# ESC_Board_1.net
KiCad netlist of a schematic drawn in EAGLE
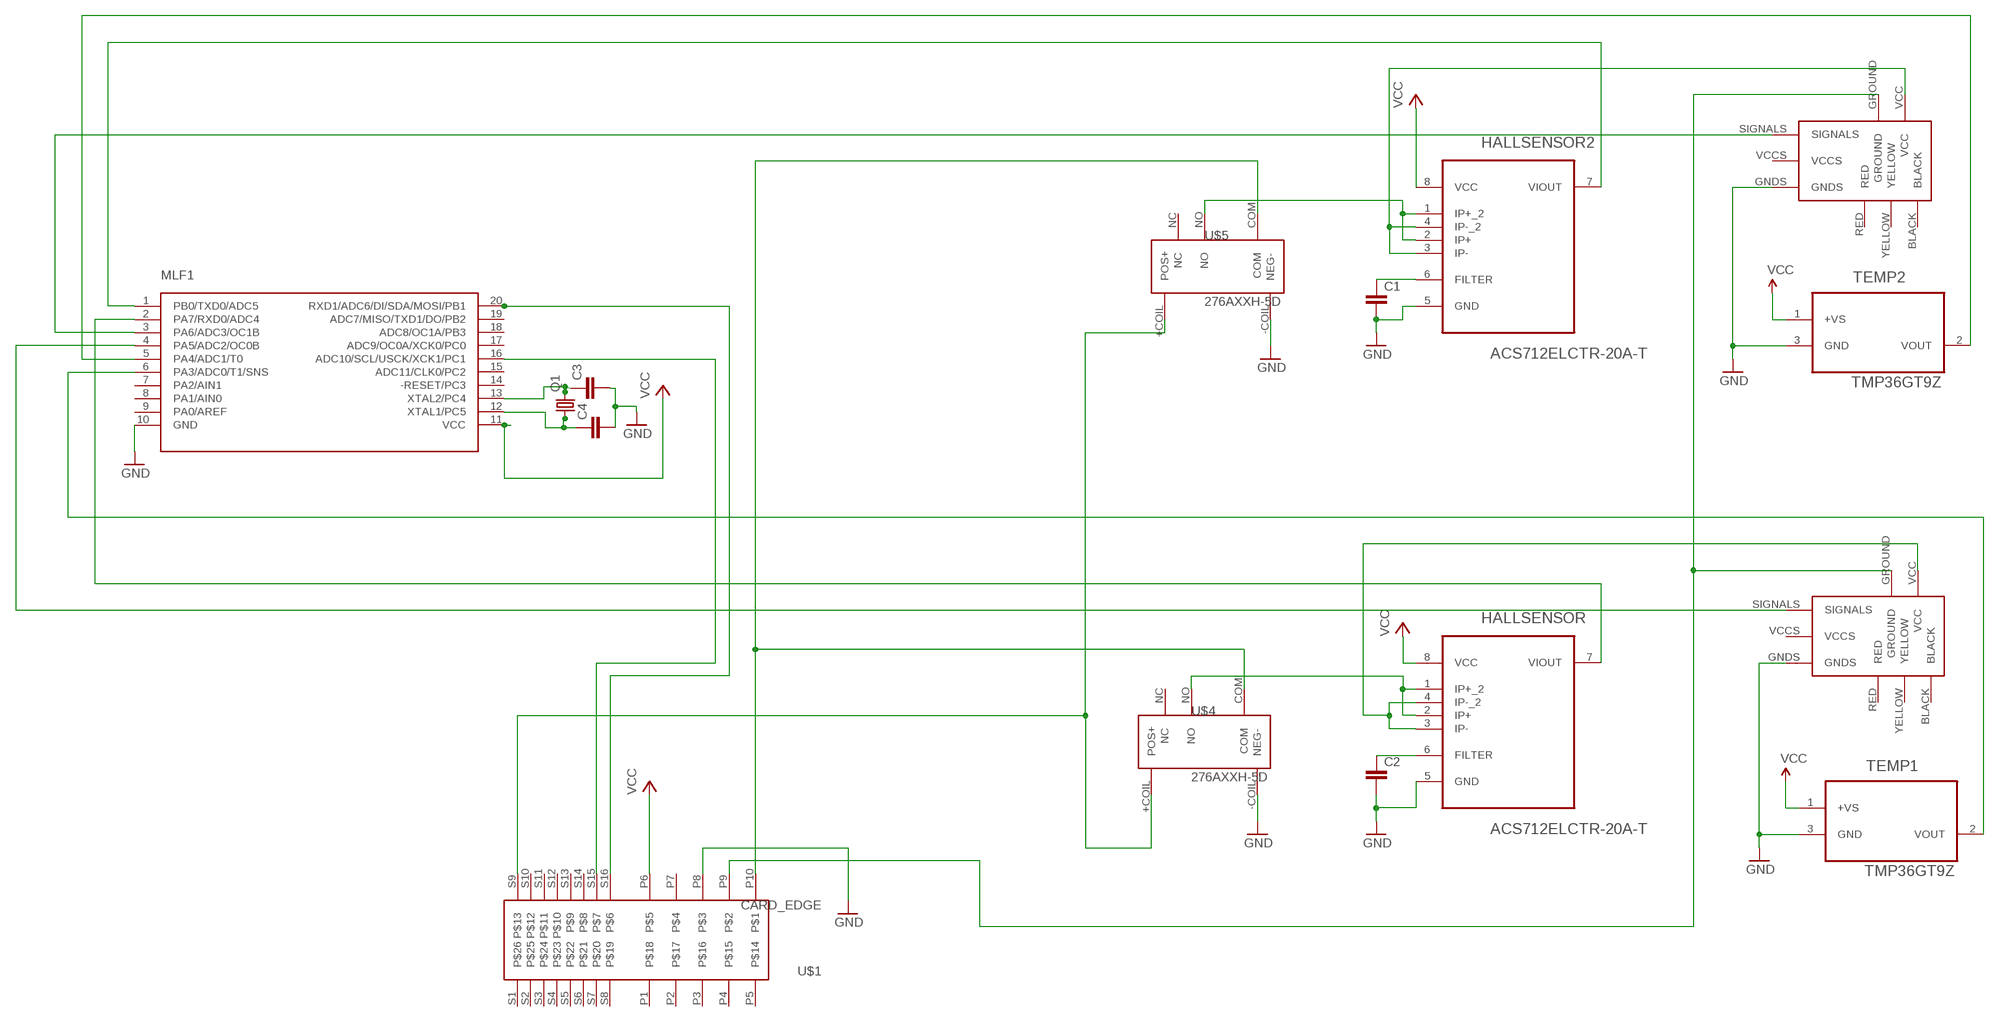
[diagram p0: schematic, sheet 1]

(export (version "E")
  (design (tool "Eeschema 10.0.6"))
  (components
    (comp (ref "C1")
      (value "CAPEZ")
      (footprint "eagle-import:CAP-PTH-SMALLEZ")
      (libsource (lib "eagle-import") (part "CAPEZ"))
    )
    (comp (ref "C2")
      (value "CAPEZ")
      (footprint "eagle-import:CAP-PTH-SMALLEZ")
      (libsource (lib "eagle-import") (part "CAPEZ"))
    )
    (comp (ref "C3")
      (value "CAPEZ")
      (footprint "eagle-import:CAP-PTH-SMALLEZ")
      (libsource (lib "eagle-import") (part "CAPEZ"))
    )
    (comp (ref "C4")
      (value "CAPEZ")
      (footprint "eagle-import:CAP-PTH-SMALLEZ")
      (libsource (lib "eagle-import") (part "CAPEZ"))
    )
    (comp (ref "HALLSENSOR")
      (value "ACS712ELCTR-20A-T")
      (footprint "eagle-import:SOIC127P600X175-8N")
      (libsource (lib "eagle-import") (part "ACS712ELCTR-20A-T"))
    )
    (comp (ref "HALLSENSOR2")
      (value "ACS712ELCTR-20A-T")
      (footprint "eagle-import:SOIC127P600X175-8N")
      (libsource (lib "eagle-import") (part "ACS712ELCTR-20A-T"))
    )
    (comp (ref "MLF1")
      (value "ATTINY1634SOIC20")
      (footprint "eagle-import:SOIC20")
      (libsource (lib "eagle-import") (part "ATTINY1634SOIC20"))
    )
    (comp (ref "Q1")
      (value "CRYTALTC26V")
      (footprint "eagle-import:TC26V")
      (libsource (lib "eagle-import") (part "CRYTALTC26V"))
    )
    (comp (ref "TEMP1")
      (value "TMP36GT9Z")
      (footprint "eagle-import:TO127P254X533-3P")
      (libsource (lib "eagle-import") (part "TMP36GT9Z"))
    )
    (comp (ref "TEMP2")
      (value "TMP36GT9Z")
      (footprint "eagle-import:TO127P254X533-3P")
      (libsource (lib "eagle-import") (part "TMP36GT9Z"))
    )
    (comp (ref "U$1")
      (value "CARD_EDGE")
      (footprint "eagle-import:EDGE_CONNECTOR")
      (libsource (lib "eagle-import") (part "CARD_EDGE"))
    )
    (comp (ref "U$2")
      (value "ESC30A")
      (footprint "eagle-import:30AESC")
      (libsource (lib "eagle-import") (part "ESC30A"))
    )
    (comp (ref "U$3")
      (value "ESC30A")
      (footprint "eagle-import:30AESC")
      (libsource (lib "eagle-import") (part "ESC30A"))
    )
    (comp (ref "U$4")
      (value "276AXXH-5D")
      (footprint "eagle-import:276AXXH-5D")
      (libsource (lib "eagle-import") (part "276AXXH-5D"))
    )
    (comp (ref "U$5")
      (value "276AXXH-5D")
      (footprint "eagle-import:276AXXH-5D")
      (libsource (lib "eagle-import") (part "276AXXH-5D"))
    )
  )
  (nets
    (net (code "1") (name "GND") (class "Default")
      (node (ref "C1") (pin "2") (pinfunction "2_2") (pintype "passive"))
      (node (ref "C2") (pin "2") (pinfunction "2_2") (pintype "passive"))
      (node (ref "C3") (pin "2") (pinfunction "2_2") (pintype "passive"))
      (node (ref "C4") (pin "2") (pinfunction "2_2") (pintype "passive"))
      (node (ref "HALLSENSOR") (pin "5") (pinfunction "GND_5") (pintype "passive"))
      (node (ref "HALLSENSOR2") (pin "5") (pinfunction "GND_5") (pintype "passive"))
      (node (ref "MLF1") (pin "10") (pinfunction "GND_10") (pintype "power_in"))
      (node (ref "TEMP1") (pin "3") (pinfunction "GND_3") (pintype "passive"))
      (node (ref "TEMP2") (pin "3") (pinfunction "GND_3") (pintype "passive"))
      (node (ref "U$1") (pin "P8") (pinfunction "P$3_P8") (pintype "bidirectional"))
      (node (ref "U$2") (pin "GNDS") (pinfunction "GNDS_GNDS") (pintype "bidirectional"))
      (node (ref "U$3") (pin "GNDS") (pinfunction "GNDS_GNDS") (pintype "bidirectional"))
      (node (ref "U$4") (pin "-COIL") (pinfunction "NEG-_-COIL") (pintype "bidirectional"))
      (node (ref "U$5") (pin "-COIL") (pinfunction "NEG-_-COIL") (pintype "bidirectional"))
    )
    (net (code "2") (name "Net-(HALLSENSOR-FILTER)") (class "Default")
      (node (ref "C2") (pin "1") (pinfunction "1_1") (pintype "passive"))
      (node (ref "HALLSENSOR") (pin "6") (pinfunction "FILTER_6") (pintype "input"))
    )
    (net (code "3") (name "Net-(HALLSENSOR-IP+)") (class "Default")
      (node (ref "HALLSENSOR") (pin "1") (pinfunction "IP+_2_1") (pintype "input"))
      (node (ref "HALLSENSOR") (pin "2") (pinfunction "IP+_2") (pintype "input"))
      (node (ref "U$4") (pin "NO") (pinfunction "NO_NO") (pintype "bidirectional"))
    )
    (net (code "4") (name "Net-(HALLSENSOR-IP-)") (class "Default")
      (node (ref "HALLSENSOR") (pin "3") (pinfunction "IP-_3") (pintype "input"))
      (node (ref "HALLSENSOR") (pin "4") (pinfunction "IP-_2_4") (pintype "input"))
      (node (ref "U$2") (pin "VCC") (pinfunction "VCC_VCC") (pintype "bidirectional"))
    )
    (net (code "5") (name "Net-(HALLSENSOR-VIOUT)") (class "Default")
      (node (ref "HALLSENSOR") (pin "7") (pinfunction "VIOUT_7") (pintype "output"))
      (node (ref "MLF1") (pin "2") (pinfunction "PA7/RXD0/ADC4_2") (pintype "bidirectional"))
    )
    (net (code "6") (name "Net-(HALLSENSOR2-FILTER)") (class "Default")
      (node (ref "C1") (pin "1") (pinfunction "1_1") (pintype "passive"))
      (node (ref "HALLSENSOR2") (pin "6") (pinfunction "FILTER_6") (pintype "input"))
    )
    (net (code "7") (name "Net-(HALLSENSOR2-IP+)") (class "Default")
      (node (ref "HALLSENSOR2") (pin "1") (pinfunction "IP+_2_1") (pintype "input"))
      (node (ref "HALLSENSOR2") (pin "2") (pinfunction "IP+_2") (pintype "input"))
      (node (ref "U$5") (pin "NO") (pinfunction "NO_NO") (pintype "bidirectional"))
    )
    (net (code "8") (name "Net-(HALLSENSOR2-IP-)") (class "Default")
      (node (ref "HALLSENSOR2") (pin "3") (pinfunction "IP-_3") (pintype "input"))
      (node (ref "HALLSENSOR2") (pin "4") (pinfunction "IP-_2_4") (pintype "input"))
      (node (ref "U$3") (pin "VCC") (pinfunction "VCC_VCC") (pintype "bidirectional"))
    )
    (net (code "9") (name "Net-(HALLSENSOR2-VIOUT)") (class "Default")
      (node (ref "HALLSENSOR2") (pin "7") (pinfunction "VIOUT_7") (pintype "output"))
      (node (ref "MLF1") (pin "1") (pinfunction "PB0/TXD0/ADC5_1") (pintype "bidirectional"))
    )
    (net (code "10") (name "Net-(MLF1-ADC10{slash}SCL{slash}USCK{slash}XCK1{slash}PC1)") (class "Default")
      (node (ref "MLF1") (pin "16") (pinfunction "ADC10/SCL/USCK/XCK1/PC1_16") (pintype "bidirectional"))
      (node (ref "U$1") (pin "S15") (pinfunction "P$7_S15") (pintype "bidirectional"))
    )
    (net (code "11") (name "Net-(MLF1-PA3{slash}ADC0{slash}T1{slash}SNS)") (class "Default")
      (node (ref "MLF1") (pin "6") (pinfunction "PA3/ADC0/T1/SNS_6") (pintype "bidirectional"))
      (node (ref "TEMP1") (pin "2") (pinfunction "VOUT_2") (pintype "passive"))
    )
    (net (code "12") (name "Net-(MLF1-PA4{slash}ADC1{slash}T0)") (class "Default")
      (node (ref "MLF1") (pin "5") (pinfunction "PA4/ADC1/T0_5") (pintype "bidirectional"))
      (node (ref "TEMP2") (pin "2") (pinfunction "VOUT_2") (pintype "passive"))
    )
    (net (code "13") (name "Net-(MLF1-PA5{slash}ADC2{slash}OC0B)") (class "Default")
      (node (ref "MLF1") (pin "4") (pinfunction "PA5/ADC2/OC0B_4") (pintype "bidirectional"))
      (node (ref "U$2") (pin "SIGNALS") (pinfunction "SIGNALS_SIGNALS") (pintype "bidirectional"))
    )
    (net (code "14") (name "Net-(MLF1-PA6{slash}ADC3{slash}OC1B)") (class "Default")
      (node (ref "MLF1") (pin "3") (pinfunction "PA6/ADC3/OC1B_3") (pintype "bidirectional"))
      (node (ref "U$3") (pin "SIGNALS") (pinfunction "SIGNALS_SIGNALS") (pintype "bidirectional"))
    )
    (net (code "15") (name "Net-(MLF1-RXD1{slash}ADC6{slash}DI{slash}SDA{slash}MOSI{slash}PB1)") (class "Default")
      (node (ref "MLF1") (pin "20") (pinfunction "RXD1/ADC6/DI/SDA/MOSI/PB1_20") (pintype "bidirectional"))
      (node (ref "U$1") (pin "S16") (pinfunction "P$6_S16") (pintype "bidirectional"))
    )
    (net (code "16") (name "Net-(MLF1-XTAL1{slash}PC5)") (class "Default")
      (node (ref "C4") (pin "1") (pinfunction "1_1") (pintype "passive"))
      (node (ref "MLF1") (pin "12") (pinfunction "XTAL1/PC5_12") (pintype "bidirectional"))
      (node (ref "Q1") (pin "1") (pinfunction "1_1") (pintype "passive"))
    )
    (net (code "17") (name "Net-(MLF1-XTAL2{slash}PC4)") (class "Default")
      (node (ref "C3") (pin "1") (pinfunction "1_1") (pintype "passive"))
      (node (ref "MLF1") (pin "13") (pinfunction "XTAL2/PC4_13") (pintype "bidirectional"))
      (node (ref "Q1") (pin "2") (pinfunction "2_2") (pintype "passive"))
    )
    (net (code "18") (name "Net-(U$1-P$1)") (class "Default")
      (node (ref "U$1") (pin "P10") (pinfunction "P$1_P10") (pintype "bidirectional"))
      (node (ref "U$4") (pin "COM") (pinfunction "COM_COM") (pintype "bidirectional"))
      (node (ref "U$5") (pin "COM") (pinfunction "COM_COM") (pintype "bidirectional"))
    )
    (net (code "19") (name "Net-(U$1-P$2)") (class "Default")
      (node (ref "U$1") (pin "P9") (pinfunction "P$2_P9") (pintype "bidirectional"))
      (node (ref "U$2") (pin "GROUND") (pinfunction "GROUND_GROUND") (pintype "bidirectional"))
      (node (ref "U$3") (pin "GROUND") (pinfunction "GROUND_GROUND") (pintype "bidirectional"))
    )
    (net (code "20") (name "Net-(U$1-P$13)") (class "Default")
      (node (ref "U$1") (pin "S9") (pinfunction "P$13_S9") (pintype "bidirectional"))
      (node (ref "U$4") (pin "+COIL") (pinfunction "POS+_+COIL") (pintype "bidirectional"))
      (node (ref "U$5") (pin "+COIL") (pinfunction "POS+_+COIL") (pintype "bidirectional"))
    )
    (net (code "21") (name "VCC") (class "Default")
      (node (ref "HALLSENSOR") (pin "8") (pinfunction "VCC_8") (pintype "power_in"))
      (node (ref "HALLSENSOR2") (pin "8") (pinfunction "VCC_8") (pintype "power_in"))
      (node (ref "MLF1") (pin "11") (pinfunction "VCC_11") (pintype "power_in"))
      (node (ref "TEMP1") (pin "1") (pinfunction "+VS_1") (pintype "power_in"))
      (node (ref "TEMP2") (pin "1") (pinfunction "+VS_1") (pintype "power_in"))
      (node (ref "U$1") (pin "P6") (pinfunction "P$5_P6") (pintype "bidirectional"))
    )
    (net (code "22") (name "unconnected-(MLF1--RESET{slash}PC3-Pad14)") (class "Default")
      (node (ref "MLF1") (pin "14") (pinfunction "-RESET/PC3_14") (pintype "bidirectional"))
    )
    (net (code "23") (name "unconnected-(MLF1-ADC7{slash}MISO{slash}TXD1{slash}DO{slash}PB2-Pad19)") (class "Default")
      (node (ref "MLF1") (pin "19") (pinfunction "ADC7/MISO/TXD1/DO/PB2_19") (pintype "bidirectional"))
    )
    (net (code "24") (name "unconnected-(MLF1-ADC8{slash}OC1A{slash}PB3-Pad18)") (class "Default")
      (node (ref "MLF1") (pin "18") (pinfunction "ADC8/OC1A/PB3_18") (pintype "bidirectional"))
    )
    (net (code "25") (name "unconnected-(MLF1-ADC9{slash}OC0A{slash}XCK0{slash}PC0-Pad17)") (class "Default")
      (node (ref "MLF1") (pin "17") (pinfunction "ADC9/OC0A/XCK0/PC0_17") (pintype "bidirectional"))
    )
    (net (code "26") (name "unconnected-(MLF1-ADC11{slash}CLK0{slash}PC2-Pad15)") (class "Default")
      (node (ref "MLF1") (pin "15") (pinfunction "ADC11/CLK0/PC2_15") (pintype "bidirectional"))
    )
    (net (code "27") (name "unconnected-(MLF1-PA0{slash}AREF-Pad9)") (class "Default")
      (node (ref "MLF1") (pin "9") (pinfunction "PA0/AREF_9") (pintype "bidirectional"))
    )
    (net (code "28") (name "unconnected-(MLF1-PA1{slash}AIN0-Pad8)") (class "Default")
      (node (ref "MLF1") (pin "8") (pinfunction "PA1/AIN0_8") (pintype "bidirectional"))
    )
    (net (code "29") (name "unconnected-(MLF1-PA2{slash}AIN1-Pad7)") (class "Default")
      (node (ref "MLF1") (pin "7") (pinfunction "PA2/AIN1_7") (pintype "bidirectional"))
    )
    (net (code "30") (name "unconnected-(U$1-P$4-PadP7)") (class "Default")
      (node (ref "U$1") (pin "P7") (pinfunction "P$4_P7") (pintype "bidirectional"))
    )
    (net (code "31") (name "unconnected-(U$1-P$8-PadS14)") (class "Default")
      (node (ref "U$1") (pin "S14") (pinfunction "P$8_S14") (pintype "bidirectional"))
    )
    (net (code "32") (name "unconnected-(U$1-P$9-PadS13)") (class "Default")
      (node (ref "U$1") (pin "S13") (pinfunction "P$9_S13") (pintype "bidirectional"))
    )
    (net (code "33") (name "unconnected-(U$1-P$10-PadS12)") (class "Default")
      (node (ref "U$1") (pin "S12") (pinfunction "P$10_S12") (pintype "bidirectional"))
    )
    (net (code "34") (name "unconnected-(U$1-P$11-PadS11)") (class "Default")
      (node (ref "U$1") (pin "S11") (pinfunction "P$11_S11") (pintype "bidirectional"))
    )
    (net (code "35") (name "unconnected-(U$1-P$12-PadS10)") (class "Default")
      (node (ref "U$1") (pin "S10") (pinfunction "P$12_S10") (pintype "bidirectional"))
    )
    (net (code "36") (name "unconnected-(U$1-P$14-PadP5)") (class "Default")
      (node (ref "U$1") (pin "P5") (pinfunction "P$14_P5") (pintype "bidirectional"))
    )
    (net (code "37") (name "unconnected-(U$1-P$15-PadP4)") (class "Default")
      (node (ref "U$1") (pin "P4") (pinfunction "P$15_P4") (pintype "bidirectional"))
    )
    (net (code "38") (name "unconnected-(U$1-P$16-PadP3)") (class "Default")
      (node (ref "U$1") (pin "P3") (pinfunction "P$16_P3") (pintype "bidirectional"))
    )
    (net (code "39") (name "unconnected-(U$1-P$17-PadP2)") (class "Default")
      (node (ref "U$1") (pin "P2") (pinfunction "P$17_P2") (pintype "bidirectional"))
    )
    (net (code "40") (name "unconnected-(U$1-P$18-PadP1)") (class "Default")
      (node (ref "U$1") (pin "P1") (pinfunction "P$18_P1") (pintype "bidirectional"))
    )
    (net (code "41") (name "unconnected-(U$1-P$19-PadS8)") (class "Default")
      (node (ref "U$1") (pin "S8") (pinfunction "P$19_S8") (pintype "bidirectional"))
    )
    (net (code "42") (name "unconnected-(U$1-P$20-PadS7)") (class "Default")
      (node (ref "U$1") (pin "S7") (pinfunction "P$20_S7") (pintype "bidirectional"))
    )
    (net (code "43") (name "unconnected-(U$1-P$21-PadS6)") (class "Default")
      (node (ref "U$1") (pin "S6") (pinfunction "P$21_S6") (pintype "bidirectional"))
    )
    (net (code "44") (name "unconnected-(U$1-P$22-PadS5)") (class "Default")
      (node (ref "U$1") (pin "S5") (pinfunction "P$22_S5") (pintype "bidirectional"))
    )
    (net (code "45") (name "unconnected-(U$1-P$23-PadS4)") (class "Default")
      (node (ref "U$1") (pin "S4") (pinfunction "P$23_S4") (pintype "bidirectional"))
    )
    (net (code "46") (name "unconnected-(U$1-P$24-PadS3)") (class "Default")
      (node (ref "U$1") (pin "S3") (pinfunction "P$24_S3") (pintype "bidirectional"))
    )
    (net (code "47") (name "unconnected-(U$1-P$25-PadS2)") (class "Default")
      (node (ref "U$1") (pin "S2") (pinfunction "P$25_S2") (pintype "bidirectional"))
    )
    (net (code "48") (name "unconnected-(U$1-P$26-PadS1)") (class "Default")
      (node (ref "U$1") (pin "S1") (pinfunction "P$26_S1") (pintype "bidirectional"))
    )
    (net (code "49") (name "unconnected-(U$2-PadBLACK)") (class "Default")
      (node (ref "U$2") (pin "BLACK") (pinfunction "BLACK_BLACK") (pintype "bidirectional"))
    )
    (net (code "50") (name "unconnected-(U$2-PadRED)") (class "Default")
      (node (ref "U$2") (pin "RED") (pinfunction "RED_RED") (pintype "bidirectional"))
    )
    (net (code "51") (name "unconnected-(U$2-PadVCCS)") (class "Default")
      (node (ref "U$2") (pin "VCCS") (pinfunction "VCCS_VCCS") (pintype "bidirectional"))
    )
    (net (code "52") (name "unconnected-(U$2-PadYELLOW)") (class "Default")
      (node (ref "U$2") (pin "YELLOW") (pinfunction "YELLOW_YELLOW") (pintype "bidirectional"))
    )
    (net (code "53") (name "unconnected-(U$3-PadBLACK)") (class "Default")
      (node (ref "U$3") (pin "BLACK") (pinfunction "BLACK_BLACK") (pintype "bidirectional"))
    )
    (net (code "54") (name "unconnected-(U$3-PadRED)") (class "Default")
      (node (ref "U$3") (pin "RED") (pinfunction "RED_RED") (pintype "bidirectional"))
    )
    (net (code "55") (name "unconnected-(U$3-PadVCCS)") (class "Default")
      (node (ref "U$3") (pin "VCCS") (pinfunction "VCCS_VCCS") (pintype "bidirectional"))
    )
    (net (code "56") (name "unconnected-(U$3-PadYELLOW)") (class "Default")
      (node (ref "U$3") (pin "YELLOW") (pinfunction "YELLOW_YELLOW") (pintype "bidirectional"))
    )
    (net (code "57") (name "unconnected-(U$4-PadNC)") (class "Default")
      (node (ref "U$4") (pin "NC") (pinfunction "NC_NC") (pintype "bidirectional"))
    )
    (net (code "58") (name "unconnected-(U$5-PadNC)") (class "Default")
      (node (ref "U$5") (pin "NC") (pinfunction "NC_NC") (pintype "bidirectional"))
    )
  )
)
